# untitled.net
KiCad netlist of a schematic drawn in EAGLE
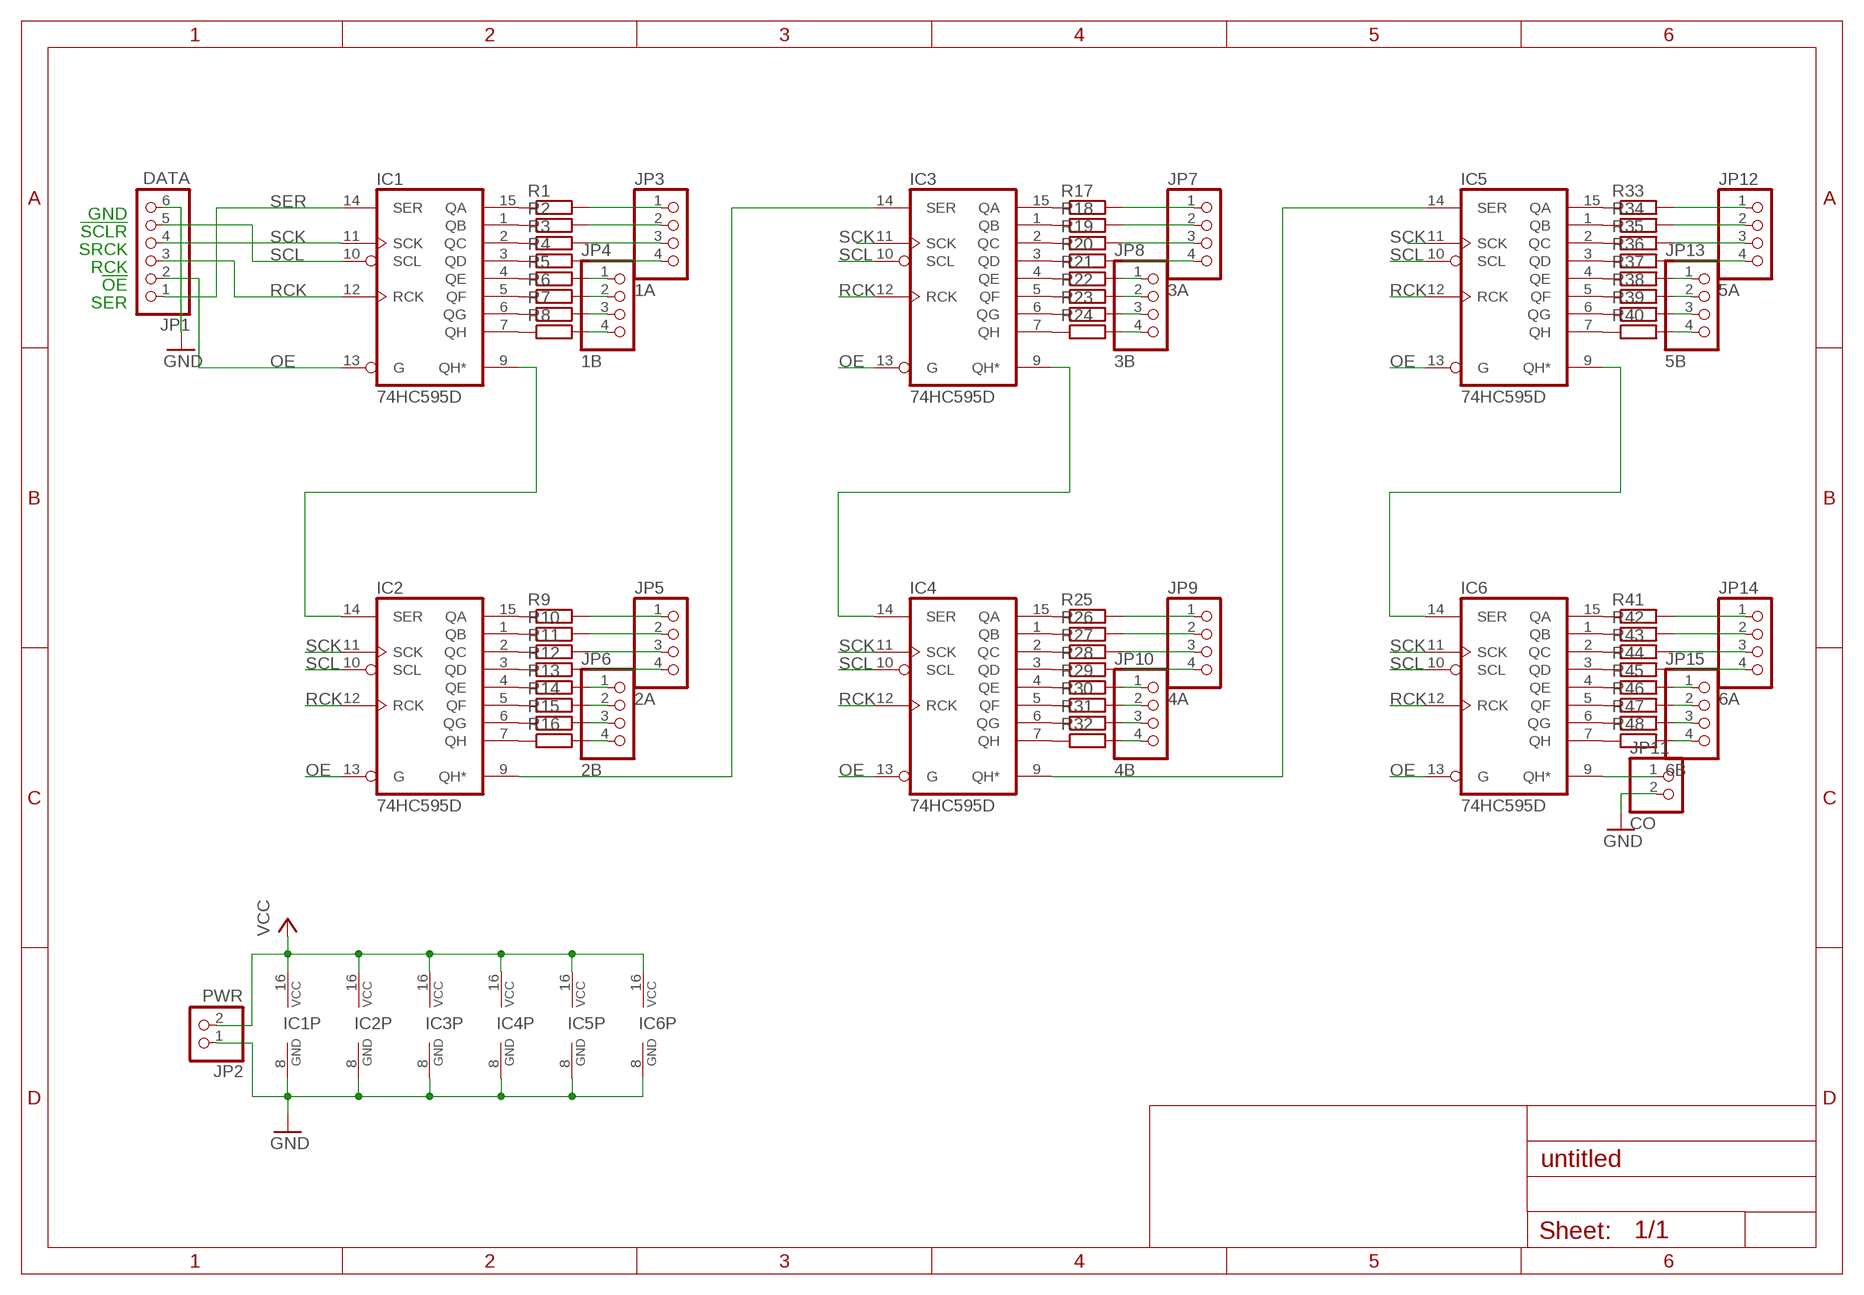
[diagram p0: schematic, sheet 1]

(export (version "E")
  (design (tool "Eeschema 10.0.6"))
  (components
    (comp (ref "IC1")
      (value "74HC595D")
      (footprint "eagle-import:SO16")
      (libsource (lib "eagle-import") (part "74595DHC"))
    )
    (comp (ref "IC2")
      (value "74HC595D")
      (footprint "eagle-import:SO16")
      (libsource (lib "eagle-import") (part "74595DHC"))
    )
    (comp (ref "IC3")
      (value "74HC595D")
      (footprint "eagle-import:SO16")
      (libsource (lib "eagle-import") (part "74595DHC"))
    )
    (comp (ref "IC4")
      (value "74HC595D")
      (footprint "eagle-import:SO16")
      (libsource (lib "eagle-import") (part "74595DHC"))
    )
    (comp (ref "IC5")
      (value "74HC595D")
      (footprint "eagle-import:SO16")
      (libsource (lib "eagle-import") (part "74595DHC"))
    )
    (comp (ref "IC6")
      (value "74HC595D")
      (footprint "eagle-import:SO16")
      (libsource (lib "eagle-import") (part "74595DHC"))
    )
    (comp (ref "JP1")
      (value "DATA")
      (footprint "eagle-import:1X06")
      (libsource (lib "eagle-import") (part "PINHD-1X6"))
    )
    (comp (ref "JP2")
      (value "PWR")
      (footprint "eagle-import:1X02")
      (libsource (lib "eagle-import") (part "PINHD-1X2"))
    )
    (comp (ref "JP3")
      (value "1A")
      (footprint "eagle-import:1X04")
      (libsource (lib "eagle-import") (part "PINHD-1X4"))
    )
    (comp (ref "JP4")
      (value "1B")
      (footprint "eagle-import:1X04")
      (libsource (lib "eagle-import") (part "PINHD-1X4"))
    )
    (comp (ref "JP5")
      (value "2A")
      (footprint "eagle-import:1X04")
      (libsource (lib "eagle-import") (part "PINHD-1X4"))
    )
    (comp (ref "JP6")
      (value "2B")
      (footprint "eagle-import:1X04")
      (libsource (lib "eagle-import") (part "PINHD-1X4"))
    )
    (comp (ref "JP7")
      (value "3A")
      (footprint "eagle-import:1X04")
      (libsource (lib "eagle-import") (part "PINHD-1X4"))
    )
    (comp (ref "JP8")
      (value "3B")
      (footprint "eagle-import:1X04")
      (libsource (lib "eagle-import") (part "PINHD-1X4"))
    )
    (comp (ref "JP9")
      (value "4A")
      (footprint "eagle-import:1X04")
      (libsource (lib "eagle-import") (part "PINHD-1X4"))
    )
    (comp (ref "JP10")
      (value "4B")
      (footprint "eagle-import:1X04")
      (libsource (lib "eagle-import") (part "PINHD-1X4"))
    )
    (comp (ref "JP11")
      (value "CO")
      (footprint "eagle-import:1X02")
      (libsource (lib "eagle-import") (part "PINHD-1X2"))
    )
    (comp (ref "JP12")
      (value "5A")
      (footprint "eagle-import:1X04")
      (libsource (lib "eagle-import") (part "PINHD-1X4"))
    )
    (comp (ref "JP13")
      (value "5B")
      (footprint "eagle-import:1X04")
      (libsource (lib "eagle-import") (part "PINHD-1X4"))
    )
    (comp (ref "JP14")
      (value "6A")
      (footprint "eagle-import:1X04")
      (libsource (lib "eagle-import") (part "PINHD-1X4"))
    )
    (comp (ref "JP15")
      (value "6B")
      (footprint "eagle-import:1X04")
      (libsource (lib "eagle-import") (part "PINHD-1X4"))
    )
    (comp (ref "R1")
      (value "R-EU_R0805")
      (footprint "eagle-import:R0805")
      (libsource (lib "eagle-import") (part "R-EU_R0805"))
    )
    (comp (ref "R2")
      (value "R-EU_R0805")
      (footprint "eagle-import:R0805")
      (libsource (lib "eagle-import") (part "R-EU_R0805"))
    )
    (comp (ref "R3")
      (value "R-EU_R0805")
      (footprint "eagle-import:R0805")
      (libsource (lib "eagle-import") (part "R-EU_R0805"))
    )
    (comp (ref "R4")
      (value "R-EU_R0805")
      (footprint "eagle-import:R0805")
      (libsource (lib "eagle-import") (part "R-EU_R0805"))
    )
    (comp (ref "R5")
      (value "R-EU_R0805")
      (footprint "eagle-import:R0805")
      (libsource (lib "eagle-import") (part "R-EU_R0805"))
    )
    (comp (ref "R6")
      (value "R-EU_R0805")
      (footprint "eagle-import:R0805")
      (libsource (lib "eagle-import") (part "R-EU_R0805"))
    )
    (comp (ref "R7")
      (value "R-EU_R0805")
      (footprint "eagle-import:R0805")
      (libsource (lib "eagle-import") (part "R-EU_R0805"))
    )
    (comp (ref "R8")
      (value "R-EU_R0805")
      (footprint "eagle-import:R0805")
      (libsource (lib "eagle-import") (part "R-EU_R0805"))
    )
    (comp (ref "R9")
      (value "R-EU_R0805")
      (footprint "eagle-import:R0805")
      (libsource (lib "eagle-import") (part "R-EU_R0805"))
    )
    (comp (ref "R10")
      (value "R-EU_R0805")
      (footprint "eagle-import:R0805")
      (libsource (lib "eagle-import") (part "R-EU_R0805"))
    )
    (comp (ref "R11")
      (value "R-EU_R0805")
      (footprint "eagle-import:R0805")
      (libsource (lib "eagle-import") (part "R-EU_R0805"))
    )
    (comp (ref "R12")
      (value "R-EU_R0805")
      (footprint "eagle-import:R0805")
      (libsource (lib "eagle-import") (part "R-EU_R0805"))
    )
    (comp (ref "R13")
      (value "R-EU_R0805")
      (footprint "eagle-import:R0805")
      (libsource (lib "eagle-import") (part "R-EU_R0805"))
    )
    (comp (ref "R14")
      (value "R-EU_R0805")
      (footprint "eagle-import:R0805")
      (libsource (lib "eagle-import") (part "R-EU_R0805"))
    )
    (comp (ref "R15")
      (value "R-EU_R0805")
      (footprint "eagle-import:R0805")
      (libsource (lib "eagle-import") (part "R-EU_R0805"))
    )
    (comp (ref "R16")
      (value "R-EU_R0805")
      (footprint "eagle-import:R0805")
      (libsource (lib "eagle-import") (part "R-EU_R0805"))
    )
    (comp (ref "R17")
      (value "R-EU_R0805")
      (footprint "eagle-import:R0805")
      (libsource (lib "eagle-import") (part "R-EU_R0805"))
    )
    (comp (ref "R18")
      (value "R-EU_R0805")
      (footprint "eagle-import:R0805")
      (libsource (lib "eagle-import") (part "R-EU_R0805"))
    )
    (comp (ref "R19")
      (value "R-EU_R0805")
      (footprint "eagle-import:R0805")
      (libsource (lib "eagle-import") (part "R-EU_R0805"))
    )
    (comp (ref "R20")
      (value "R-EU_R0805")
      (footprint "eagle-import:R0805")
      (libsource (lib "eagle-import") (part "R-EU_R0805"))
    )
    (comp (ref "R21")
      (value "R-EU_R0805")
      (footprint "eagle-import:R0805")
      (libsource (lib "eagle-import") (part "R-EU_R0805"))
    )
    (comp (ref "R22")
      (value "R-EU_R0805")
      (footprint "eagle-import:R0805")
      (libsource (lib "eagle-import") (part "R-EU_R0805"))
    )
    (comp (ref "R23")
      (value "R-EU_R0805")
      (footprint "eagle-import:R0805")
      (libsource (lib "eagle-import") (part "R-EU_R0805"))
    )
    (comp (ref "R24")
      (value "R-EU_R0805")
      (footprint "eagle-import:R0805")
      (libsource (lib "eagle-import") (part "R-EU_R0805"))
    )
    (comp (ref "R25")
      (value "R-EU_R0805")
      (footprint "eagle-import:R0805")
      (libsource (lib "eagle-import") (part "R-EU_R0805"))
    )
    (comp (ref "R26")
      (value "R-EU_R0805")
      (footprint "eagle-import:R0805")
      (libsource (lib "eagle-import") (part "R-EU_R0805"))
    )
    (comp (ref "R27")
      (value "R-EU_R0805")
      (footprint "eagle-import:R0805")
      (libsource (lib "eagle-import") (part "R-EU_R0805"))
    )
    (comp (ref "R28")
      (value "R-EU_R0805")
      (footprint "eagle-import:R0805")
      (libsource (lib "eagle-import") (part "R-EU_R0805"))
    )
    (comp (ref "R29")
      (value "R-EU_R0805")
      (footprint "eagle-import:R0805")
      (libsource (lib "eagle-import") (part "R-EU_R0805"))
    )
    (comp (ref "R30")
      (value "R-EU_R0805")
      (footprint "eagle-import:R0805")
      (libsource (lib "eagle-import") (part "R-EU_R0805"))
    )
    (comp (ref "R31")
      (value "R-EU_R0805")
      (footprint "eagle-import:R0805")
      (libsource (lib "eagle-import") (part "R-EU_R0805"))
    )
    (comp (ref "R32")
      (value "R-EU_R0805")
      (footprint "eagle-import:R0805")
      (libsource (lib "eagle-import") (part "R-EU_R0805"))
    )
    (comp (ref "R33")
      (value "R-EU_R0805")
      (footprint "eagle-import:R0805")
      (libsource (lib "eagle-import") (part "R-EU_R0805"))
    )
    (comp (ref "R34")
      (value "R-EU_R0805")
      (footprint "eagle-import:R0805")
      (libsource (lib "eagle-import") (part "R-EU_R0805"))
    )
    (comp (ref "R35")
      (value "R-EU_R0805")
      (footprint "eagle-import:R0805")
      (libsource (lib "eagle-import") (part "R-EU_R0805"))
    )
    (comp (ref "R36")
      (value "R-EU_R0805")
      (footprint "eagle-import:R0805")
      (libsource (lib "eagle-import") (part "R-EU_R0805"))
    )
    (comp (ref "R37")
      (value "R-EU_R0805")
      (footprint "eagle-import:R0805")
      (libsource (lib "eagle-import") (part "R-EU_R0805"))
    )
    (comp (ref "R38")
      (value "R-EU_R0805")
      (footprint "eagle-import:R0805")
      (libsource (lib "eagle-import") (part "R-EU_R0805"))
    )
    (comp (ref "R39")
      (value "R-EU_R0805")
      (footprint "eagle-import:R0805")
      (libsource (lib "eagle-import") (part "R-EU_R0805"))
    )
    (comp (ref "R40")
      (value "R-EU_R0805")
      (footprint "eagle-import:R0805")
      (libsource (lib "eagle-import") (part "R-EU_R0805"))
    )
    (comp (ref "R41")
      (value "R-EU_R0805")
      (footprint "eagle-import:R0805")
      (libsource (lib "eagle-import") (part "R-EU_R0805"))
    )
    (comp (ref "R42")
      (value "R-EU_R0805")
      (footprint "eagle-import:R0805")
      (libsource (lib "eagle-import") (part "R-EU_R0805"))
    )
    (comp (ref "R43")
      (value "R-EU_R0805")
      (footprint "eagle-import:R0805")
      (libsource (lib "eagle-import") (part "R-EU_R0805"))
    )
    (comp (ref "R44")
      (value "R-EU_R0805")
      (footprint "eagle-import:R0805")
      (libsource (lib "eagle-import") (part "R-EU_R0805"))
    )
    (comp (ref "R45")
      (value "R-EU_R0805")
      (footprint "eagle-import:R0805")
      (libsource (lib "eagle-import") (part "R-EU_R0805"))
    )
    (comp (ref "R46")
      (value "R-EU_R0805")
      (footprint "eagle-import:R0805")
      (libsource (lib "eagle-import") (part "R-EU_R0805"))
    )
    (comp (ref "R47")
      (value "R-EU_R0805")
      (footprint "eagle-import:R0805")
      (libsource (lib "eagle-import") (part "R-EU_R0805"))
    )
    (comp (ref "R48")
      (value "R-EU_R0805")
      (footprint "eagle-import:R0805")
      (libsource (lib "eagle-import") (part "R-EU_R0805"))
    )
  )
  (nets
    (net (code "1") (name "/OE") (class "Default")
      (node (ref "IC1") (pin "13") (pinfunction "G_13") (pintype "input"))
      (node (ref "IC2") (pin "13") (pinfunction "G_13") (pintype "input"))
      (node (ref "IC3") (pin "13") (pinfunction "G_13") (pintype "input"))
      (node (ref "IC4") (pin "13") (pinfunction "G_13") (pintype "input"))
      (node (ref "IC5") (pin "13") (pinfunction "G_13") (pintype "input"))
      (node (ref "IC6") (pin "13") (pinfunction "G_13") (pintype "input"))
      (node (ref "JP1") (pin "2") (pinfunction "2_2") (pintype "passive"))
    )
    (net (code "2") (name "/RCK") (class "Default")
      (node (ref "IC1") (pin "12") (pinfunction "RCK_12") (pintype "input"))
      (node (ref "IC2") (pin "12") (pinfunction "RCK_12") (pintype "input"))
      (node (ref "IC3") (pin "12") (pinfunction "RCK_12") (pintype "input"))
      (node (ref "IC4") (pin "12") (pinfunction "RCK_12") (pintype "input"))
      (node (ref "IC5") (pin "12") (pinfunction "RCK_12") (pintype "input"))
      (node (ref "IC6") (pin "12") (pinfunction "RCK_12") (pintype "input"))
      (node (ref "JP1") (pin "3") (pinfunction "3_3") (pintype "passive"))
    )
    (net (code "3") (name "/SCK") (class "Default")
      (node (ref "IC1") (pin "11") (pinfunction "SCK_11") (pintype "input"))
      (node (ref "IC2") (pin "11") (pinfunction "SCK_11") (pintype "input"))
      (node (ref "IC3") (pin "11") (pinfunction "SCK_11") (pintype "input"))
      (node (ref "IC4") (pin "11") (pinfunction "SCK_11") (pintype "input"))
      (node (ref "IC5") (pin "11") (pinfunction "SCK_11") (pintype "input"))
      (node (ref "IC6") (pin "11") (pinfunction "SCK_11") (pintype "input"))
      (node (ref "JP1") (pin "4") (pinfunction "4_4") (pintype "passive"))
    )
    (net (code "4") (name "/SCL") (class "Default")
      (node (ref "IC1") (pin "10") (pinfunction "SCL_10") (pintype "input"))
      (node (ref "IC2") (pin "10") (pinfunction "SCL_10") (pintype "input"))
      (node (ref "IC3") (pin "10") (pinfunction "SCL_10") (pintype "input"))
      (node (ref "IC4") (pin "10") (pinfunction "SCL_10") (pintype "input"))
      (node (ref "IC5") (pin "10") (pinfunction "SCL_10") (pintype "input"))
      (node (ref "IC6") (pin "10") (pinfunction "SCL_10") (pintype "input"))
      (node (ref "JP1") (pin "5") (pinfunction "5_5") (pintype "passive"))
    )
    (net (code "5") (name "/SER") (class "Default")
      (node (ref "IC1") (pin "14") (pinfunction "SER_14") (pintype "input"))
      (node (ref "JP1") (pin "1") (pinfunction "1_1") (pintype "passive"))
    )
    (net (code "6") (name "GND") (class "Default")
      (node (ref "IC1") (pin "8") (pinfunction "GND_8") (pintype "power_in"))
      (node (ref "IC2") (pin "8") (pinfunction "GND_8") (pintype "power_in"))
      (node (ref "IC3") (pin "8") (pinfunction "GND_8") (pintype "power_in"))
      (node (ref "IC4") (pin "8") (pinfunction "GND_8") (pintype "power_in"))
      (node (ref "IC5") (pin "8") (pinfunction "GND_8") (pintype "power_in"))
      (node (ref "IC6") (pin "8") (pinfunction "GND_8") (pintype "power_in"))
      (node (ref "JP1") (pin "6") (pinfunction "6_6") (pintype "passive"))
      (node (ref "JP11") (pin "2") (pinfunction "2_2") (pintype "passive"))
      (node (ref "JP2") (pin "1") (pinfunction "1_1") (pintype "passive"))
    )
    (net (code "7") (name "Net-(IC1A-QA)") (class "Default")
      (node (ref "IC1") (pin "15") (pinfunction "QA_15") (pintype "tri_state"))
      (node (ref "R1") (pin "1") (pinfunction "1_1") (pintype "passive"))
    )
    (net (code "8") (name "Net-(IC1A-QB)") (class "Default")
      (node (ref "IC1") (pin "1") (pinfunction "QB_1") (pintype "tri_state"))
      (node (ref "R2") (pin "1") (pinfunction "1_1") (pintype "passive"))
    )
    (net (code "9") (name "Net-(IC1A-QC)") (class "Default")
      (node (ref "IC1") (pin "2") (pinfunction "QC_2") (pintype "tri_state"))
      (node (ref "R3") (pin "1") (pinfunction "1_1") (pintype "passive"))
    )
    (net (code "10") (name "Net-(IC1A-QD)") (class "Default")
      (node (ref "IC1") (pin "3") (pinfunction "QD_3") (pintype "tri_state"))
      (node (ref "R4") (pin "1") (pinfunction "1_1") (pintype "passive"))
    )
    (net (code "11") (name "Net-(IC1A-QE)") (class "Default")
      (node (ref "IC1") (pin "4") (pinfunction "QE_4") (pintype "tri_state"))
      (node (ref "R5") (pin "1") (pinfunction "1_1") (pintype "passive"))
    )
    (net (code "12") (name "Net-(IC1A-QF)") (class "Default")
      (node (ref "IC1") (pin "5") (pinfunction "QF_5") (pintype "tri_state"))
      (node (ref "R6") (pin "1") (pinfunction "1_1") (pintype "passive"))
    )
    (net (code "13") (name "Net-(IC1A-QG)") (class "Default")
      (node (ref "IC1") (pin "6") (pinfunction "QG_6") (pintype "tri_state"))
      (node (ref "R7") (pin "1") (pinfunction "1_1") (pintype "passive"))
    )
    (net (code "14") (name "Net-(IC1A-QH)") (class "Default")
      (node (ref "IC1") (pin "7") (pinfunction "QH_7") (pintype "tri_state"))
      (node (ref "R8") (pin "1") (pinfunction "1_1") (pintype "passive"))
    )
    (net (code "15") (name "Net-(IC1A-QH*)") (class "Default")
      (node (ref "IC1") (pin "9") (pinfunction "QH*_9") (pintype "tri_state"))
      (node (ref "IC2") (pin "14") (pinfunction "SER_14") (pintype "input"))
    )
    (net (code "16") (name "Net-(IC2A-QA)") (class "Default")
      (node (ref "IC2") (pin "15") (pinfunction "QA_15") (pintype "tri_state"))
      (node (ref "R9") (pin "1") (pinfunction "1_1") (pintype "passive"))
    )
    (net (code "17") (name "Net-(IC2A-QB)") (class "Default")
      (node (ref "IC2") (pin "1") (pinfunction "QB_1") (pintype "tri_state"))
      (node (ref "R10") (pin "1") (pinfunction "1_1") (pintype "passive"))
    )
    (net (code "18") (name "Net-(IC2A-QC)") (class "Default")
      (node (ref "IC2") (pin "2") (pinfunction "QC_2") (pintype "tri_state"))
      (node (ref "R11") (pin "1") (pinfunction "1_1") (pintype "passive"))
    )
    (net (code "19") (name "Net-(IC2A-QD)") (class "Default")
      (node (ref "IC2") (pin "3") (pinfunction "QD_3") (pintype "tri_state"))
      (node (ref "R12") (pin "1") (pinfunction "1_1") (pintype "passive"))
    )
    (net (code "20") (name "Net-(IC2A-QE)") (class "Default")
      (node (ref "IC2") (pin "4") (pinfunction "QE_4") (pintype "tri_state"))
      (node (ref "R13") (pin "1") (pinfunction "1_1") (pintype "passive"))
    )
    (net (code "21") (name "Net-(IC2A-QF)") (class "Default")
      (node (ref "IC2") (pin "5") (pinfunction "QF_5") (pintype "tri_state"))
      (node (ref "R14") (pin "1") (pinfunction "1_1") (pintype "passive"))
    )
    (net (code "22") (name "Net-(IC2A-QG)") (class "Default")
      (node (ref "IC2") (pin "6") (pinfunction "QG_6") (pintype "tri_state"))
      (node (ref "R15") (pin "1") (pinfunction "1_1") (pintype "passive"))
    )
    (net (code "23") (name "Net-(IC2A-QH)") (class "Default")
      (node (ref "IC2") (pin "7") (pinfunction "QH_7") (pintype "tri_state"))
      (node (ref "R16") (pin "1") (pinfunction "1_1") (pintype "passive"))
    )
    (net (code "24") (name "Net-(IC2A-QH*)") (class "Default")
      (node (ref "IC2") (pin "9") (pinfunction "QH*_9") (pintype "tri_state"))
      (node (ref "IC3") (pin "14") (pinfunction "SER_14") (pintype "input"))
    )
    (net (code "25") (name "Net-(IC3A-QA)") (class "Default")
      (node (ref "IC3") (pin "15") (pinfunction "QA_15") (pintype "tri_state"))
      (node (ref "R17") (pin "1") (pinfunction "1_1") (pintype "passive"))
    )
    (net (code "26") (name "Net-(IC3A-QB)") (class "Default")
      (node (ref "IC3") (pin "1") (pinfunction "QB_1") (pintype "tri_state"))
      (node (ref "R18") (pin "1") (pinfunction "1_1") (pintype "passive"))
    )
    (net (code "27") (name "Net-(IC3A-QC)") (class "Default")
      (node (ref "IC3") (pin "2") (pinfunction "QC_2") (pintype "tri_state"))
      (node (ref "R19") (pin "1") (pinfunction "1_1") (pintype "passive"))
    )
    (net (code "28") (name "Net-(IC3A-QD)") (class "Default")
      (node (ref "IC3") (pin "3") (pinfunction "QD_3") (pintype "tri_state"))
      (node (ref "R20") (pin "1") (pinfunction "1_1") (pintype "passive"))
    )
    (net (code "29") (name "Net-(IC3A-QE)") (class "Default")
      (node (ref "IC3") (pin "4") (pinfunction "QE_4") (pintype "tri_state"))
      (node (ref "R21") (pin "1") (pinfunction "1_1") (pintype "passive"))
    )
    (net (code "30") (name "Net-(IC3A-QF)") (class "Default")
      (node (ref "IC3") (pin "5") (pinfunction "QF_5") (pintype "tri_state"))
      (node (ref "R22") (pin "1") (pinfunction "1_1") (pintype "passive"))
    )
    (net (code "31") (name "Net-(IC3A-QG)") (class "Default")
      (node (ref "IC3") (pin "6") (pinfunction "QG_6") (pintype "tri_state"))
      (node (ref "R23") (pin "1") (pinfunction "1_1") (pintype "passive"))
    )
    (net (code "32") (name "Net-(IC3A-QH)") (class "Default")
      (node (ref "IC3") (pin "7") (pinfunction "QH_7") (pintype "tri_state"))
      (node (ref "R24") (pin "1") (pinfunction "1_1") (pintype "passive"))
    )
    (net (code "33") (name "Net-(IC3A-QH*)") (class "Default")
      (node (ref "IC3") (pin "9") (pinfunction "QH*_9") (pintype "tri_state"))
      (node (ref "IC4") (pin "14") (pinfunction "SER_14") (pintype "input"))
    )
    (net (code "34") (name "Net-(IC4A-QA)") (class "Default")
      (node (ref "IC4") (pin "15") (pinfunction "QA_15") (pintype "tri_state"))
      (node (ref "R25") (pin "1") (pinfunction "1_1") (pintype "passive"))
    )
    (net (code "35") (name "Net-(IC4A-QB)") (class "Default")
      (node (ref "IC4") (pin "1") (pinfunction "QB_1") (pintype "tri_state"))
      (node (ref "R26") (pin "1") (pinfunction "1_1") (pintype "passive"))
    )
    (net (code "36") (name "Net-(IC4A-QC)") (class "Default")
      (node (ref "IC4") (pin "2") (pinfunction "QC_2") (pintype "tri_state"))
      (node (ref "R27") (pin "1") (pinfunction "1_1") (pintype "passive"))
    )
    (net (code "37") (name "Net-(IC4A-QD)") (class "Default")
      (node (ref "IC4") (pin "3") (pinfunction "QD_3") (pintype "tri_state"))
      (node (ref "R28") (pin "1") (pinfunction "1_1") (pintype "passive"))
    )
    (net (code "38") (name "Net-(IC4A-QE)") (class "Default")
      (node (ref "IC4") (pin "4") (pinfunction "QE_4") (pintype "tri_state"))
      (node (ref "R29") (pin "1") (pinfunction "1_1") (pintype "passive"))
    )
    (net (code "39") (name "Net-(IC4A-QF)") (class "Default")
      (node (ref "IC4") (pin "5") (pinfunction "QF_5") (pintype "tri_state"))
      (node (ref "R30") (pin "1") (pinfunction "1_1") (pintype "passive"))
    )
    (net (code "40") (name "Net-(IC4A-QG)") (class "Default")
      (node (ref "IC4") (pin "6") (pinfunction "QG_6") (pintype "tri_state"))
      (node (ref "R31") (pin "1") (pinfunction "1_1") (pintype "passive"))
    )
    (net (code "41") (name "Net-(IC4A-QH)") (class "Default")
      (node (ref "IC4") (pin "7") (pinfunction "QH_7") (pintype "tri_state"))
      (node (ref "R32") (pin "1") (pinfunction "1_1") (pintype "passive"))
    )
    (net (code "42") (name "Net-(IC4A-QH*)") (class "Default")
      (node (ref "IC4") (pin "9") (pinfunction "QH*_9") (pintype "tri_state"))
      (node (ref "IC5") (pin "14") (pinfunction "SER_14") (pintype "input"))
    )
    (net (code "43") (name "Net-(IC5A-QA)") (class "Default")
      (node (ref "IC5") (pin "15") (pinfunction "QA_15") (pintype "tri_state"))
      (node (ref "R33") (pin "1") (pinfunction "1_1") (pintype "passive"))
    )
    (net (code "44") (name "Net-(IC5A-QB)") (class "Default")
      (node (ref "IC5") (pin "1") (pinfunction "QB_1") (pintype "tri_state"))
      (node (ref "R34") (pin "1") (pinfunction "1_1") (pintype "passive"))
    )
    (net (code "45") (name "Net-(IC5A-QC)") (class "Default")
      (node (ref "IC5") (pin "2") (pinfunction "QC_2") (pintype "tri_state"))
      (node (ref "R35") (pin "1") (pinfunction "1_1") (pintype "passive"))
    )
    (net (code "46") (name "Net-(IC5A-QD)") (class "Default")
      (node (ref "IC5") (pin "3") (pinfunction "QD_3") (pintype "tri_state"))
      (node (ref "R36") (pin "1") (pinfunction "1_1") (pintype "passive"))
    )
    (net (code "47") (name "Net-(IC5A-QE)") (class "Default")
      (node (ref "IC5") (pin "4") (pinfunction "QE_4") (pintype "tri_state"))
      (node (ref "R37") (pin "1") (pinfunction "1_1") (pintype "passive"))
    )
    (net (code "48") (name "Net-(IC5A-QF)") (class "Default")
      (node (ref "IC5") (pin "5") (pinfunction "QF_5") (pintype "tri_state"))
      (node (ref "R38") (pin "1") (pinfunction "1_1") (pintype "passive"))
    )
    (net (code "49") (name "Net-(IC5A-QG)") (class "Default")
      (node (ref "IC5") (pin "6") (pinfunction "QG_6") (pintype "tri_state"))
      (node (ref "R39") (pin "1") (pinfunction "1_1") (pintype "passive"))
    )
    (net (code "50") (name "Net-(IC5A-QH)") (class "Default")
      (node (ref "IC5") (pin "7") (pinfunction "QH_7") (pintype "tri_state"))
      (node (ref "R40") (pin "1") (pinfunction "1_1") (pintype "passive"))
    )
    (net (code "51") (name "Net-(IC5A-QH*)") (class "Default")
      (node (ref "IC5") (pin "9") (pinfunction "QH*_9") (pintype "tri_state"))
      (node (ref "IC6") (pin "14") (pinfunction "SER_14") (pintype "input"))
    )
    (net (code "52") (name "Net-(IC6A-QA)") (class "Default")
      (node (ref "IC6") (pin "15") (pinfunction "QA_15") (pintype "tri_state"))
      (node (ref "R41") (pin "1") (pinfunction "1_1") (pintype "passive"))
    )
    (net (code "53") (name "Net-(IC6A-QB)") (class "Default")
      (node (ref "IC6") (pin "1") (pinfunction "QB_1") (pintype "tri_state"))
      (node (ref "R42") (pin "1") (pinfunction "1_1") (pintype "passive"))
    )
    (net (code "54") (name "Net-(IC6A-QC)") (class "Default")
      (node (ref "IC6") (pin "2") (pinfunction "QC_2") (pintype "tri_state"))
      (node (ref "R43") (pin "1") (pinfunction "1_1") (pintype "passive"))
    )
    (net (code "55") (name "Net-(IC6A-QD)") (class "Default")
      (node (ref "IC6") (pin "3") (pinfunction "QD_3") (pintype "tri_state"))
      (node (ref "R44") (pin "1") (pinfunction "1_1") (pintype "passive"))
    )
    (net (code "56") (name "Net-(IC6A-QE)") (class "Default")
      (node (ref "IC6") (pin "4") (pinfunction "QE_4") (pintype "tri_state"))
      (node (ref "R45") (pin "1") (pinfunction "1_1") (pintype "passive"))
    )
    (net (code "57") (name "Net-(IC6A-QF)") (class "Default")
      (node (ref "IC6") (pin "5") (pinfunction "QF_5") (pintype "tri_state"))
      (node (ref "R46") (pin "1") (pinfunction "1_1") (pintype "passive"))
    )
    (net (code "58") (name "Net-(IC6A-QG)") (class "Default")
      (node (ref "IC6") (pin "6") (pinfunction "QG_6") (pintype "tri_state"))
      (node (ref "R47") (pin "1") (pinfunction "1_1") (pintype "passive"))
    )
    (net (code "59") (name "Net-(IC6A-QH)") (class "Default")
      (node (ref "IC6") (pin "7") (pinfunction "QH_7") (pintype "tri_state"))
      (node (ref "R48") (pin "1") (pinfunction "1_1") (pintype "passive"))
    )
    (net (code "60") (name "Net-(IC6A-QH*)") (class "Default")
      (node (ref "IC6") (pin "9") (pinfunction "QH*_9") (pintype "tri_state"))
      (node (ref "JP11") (pin "1") (pinfunction "1_1") (pintype "passive"))
    )
    (net (code "61") (name "Net-(JP3-Pad1)") (class "Default")
      (node (ref "JP3") (pin "1") (pinfunction "1_1") (pintype "passive"))
      (node (ref "R1") (pin "2") (pinfunction "2_2") (pintype "passive"))
    )
    (net (code "62") (name "Net-(JP3-Pad2)") (class "Default")
      (node (ref "JP3") (pin "2") (pinfunction "2_2") (pintype "passive"))
      (node (ref "R2") (pin "2") (pinfunction "2_2") (pintype "passive"))
    )
    (net (code "63") (name "Net-(JP3-Pad3)") (class "Default")
      (node (ref "JP3") (pin "3") (pinfunction "3_3") (pintype "passive"))
      (node (ref "R3") (pin "2") (pinfunction "2_2") (pintype "passive"))
    )
    (net (code "64") (name "Net-(JP3-Pad4)") (class "Default")
      (node (ref "JP3") (pin "4") (pinfunction "4_4") (pintype "passive"))
      (node (ref "R4") (pin "2") (pinfunction "2_2") (pintype "passive"))
    )
    (net (code "65") (name "Net-(JP4-Pad1)") (class "Default")
      (node (ref "JP4") (pin "1") (pinfunction "1_1") (pintype "passive"))
      (node (ref "R5") (pin "2") (pinfunction "2_2") (pintype "passive"))
    )
    (net (code "66") (name "Net-(JP4-Pad2)") (class "Default")
      (node (ref "JP4") (pin "2") (pinfunction "2_2") (pintype "passive"))
      (node (ref "R6") (pin "2") (pinfunction "2_2") (pintype "passive"))
    )
    (net (code "67") (name "Net-(JP4-Pad3)") (class "Default")
      (node (ref "JP4") (pin "3") (pinfunction "3_3") (pintype "passive"))
      (node (ref "R7") (pin "2") (pinfunction "2_2") (pintype "passive"))
    )
    (net (code "68") (name "Net-(JP4-Pad4)") (class "Default")
      (node (ref "JP4") (pin "4") (pinfunction "4_4") (pintype "passive"))
      (node (ref "R8") (pin "2") (pinfunction "2_2") (pintype "passive"))
    )
    (net (code "69") (name "Net-(JP5-Pad1)") (class "Default")
      (node (ref "JP5") (pin "1") (pinfunction "1_1") (pintype "passive"))
      (node (ref "R9") (pin "2") (pinfunction "2_2") (pintype "passive"))
    )
    (net (code "70") (name "Net-(JP5-Pad2)") (class "Default")
      (node (ref "JP5") (pin "2") (pinfunction "2_2") (pintype "passive"))
      (node (ref "R10") (pin "2") (pinfunction "2_2") (pintype "passive"))
    )
    (net (code "71") (name "Net-(JP5-Pad3)") (class "Default")
      (node (ref "JP5") (pin "3") (pinfunction "3_3") (pintype "passive"))
      (node (ref "R11") (pin "2") (pinfunction "2_2") (pintype "passive"))
    )
    (net (code "72") (name "Net-(JP5-Pad4)") (class "Default")
      (node (ref "JP5") (pin "4") (pinfunction "4_4") (pintype "passive"))
      (node (ref "R12") (pin "2") (pinfunction "2_2") (pintype "passive"))
    )
    (net (code "73") (name "Net-(JP6-Pad1)") (class "Default")
      (node (ref "JP6") (pin "1") (pinfunction "1_1") (pintype "passive"))
      (node (ref "R13") (pin "2") (pinfunction "2_2") (pintype "passive"))
    )
    (net (code "74") (name "Net-(JP6-Pad2)") (class "Default")
      (node (ref "JP6") (pin "2") (pinfunction "2_2") (pintype "passive"))
      (node (ref "R14") (pin "2") (pinfunction "2_2") (pintype "passive"))
    )
    (net (code "75") (name "Net-(JP6-Pad3)") (class "Default")
      (node (ref "JP6") (pin "3") (pinfunction "3_3") (pintype "passive"))
      (node (ref "R15") (pin "2") (pinfunction "2_2") (pintype "passive"))
    )
    (net (code "76") (name "Net-(JP6-Pad4)") (class "Default")
      (node (ref "JP6") (pin "4") (pinfunction "4_4") (pintype "passive"))
      (node (ref "R16") (pin "2") (pinfunction "2_2") (pintype "passive"))
    )
    (net (code "77") (name "Net-(JP7-Pad1)") (class "Default")
      (node (ref "JP7") (pin "1") (pinfunction "1_1") (pintype "passive"))
      (node (ref "R17") (pin "2") (pinfunction "2_2") (pintype "passive"))
    )
    (net (code "78") (name "Net-(JP7-Pad2)") (class "Default")
      (node (ref "JP7") (pin "2") (pinfunction "2_2") (pintype "passive"))
      (node (ref "R18") (pin "2") (pinfunction "2_2") (pintype "passive"))
    )
    (net (code "79") (name "Net-(JP7-Pad3)") (class "Default")
      (node (ref "JP7") (pin "3") (pinfunction "3_3") (pintype "passive"))
      (node (ref "R19") (pin "2") (pinfunction "2_2") (pintype "passive"))
    )
    (net (code "80") (name "Net-(JP7-Pad4)") (class "Default")
      (node (ref "JP7") (pin "4") (pinfunction "4_4") (pintype "passive"))
      (node (ref "R20") (pin "2") (pinfunction "2_2") (pintype "passive"))
    )
    (net (code "81") (name "Net-(JP8-Pad1)") (class "Default")
      (node (ref "JP8") (pin "1") (pinfunction "1_1") (pintype "passive"))
      (node (ref "R21") (pin "2") (pinfunction "2_2") (pintype "passive"))
    )
    (net (code "82") (name "Net-(JP8-Pad2)") (class "Default")
      (node (ref "JP8") (pin "2") (pinfunction "2_2") (pintype "passive"))
      (node (ref "R22") (pin "2") (pinfunction "2_2") (pintype "passive"))
    )
    (net (code "83") (name "Net-(JP8-Pad3)") (class "Default")
      (node (ref "JP8") (pin "3") (pinfunction "3_3") (pintype "passive"))
      (node (ref "R23") (pin "2") (pinfunction "2_2") (pintype "passive"))
    )
    (net (code "84") (name "Net-(JP8-Pad4)") (class "Default")
      (node (ref "JP8") (pin "4") (pinfunction "4_4") (pintype "passive"))
      (node (ref "R24") (pin "2") (pinfunction "2_2") (pintype "passive"))
    )
    (net (code "85") (name "Net-(JP9-Pad1)") (class "Default")
      (node (ref "JP9") (pin "1") (pinfunction "1_1") (pintype "passive"))
      (node (ref "R25") (pin "2") (pinfunction "2_2") (pintype "passive"))
    )
    (net (code "86") (name "Net-(JP9-Pad2)") (class "Default")
      (node (ref "JP9") (pin "2") (pinfunction "2_2") (pintype "passive"))
      (node (ref "R26") (pin "2") (pinfunction "2_2") (pintype "passive"))
    )
    (net (code "87") (name "Net-(JP9-Pad3)") (class "Default")
      (node (ref "JP9") (pin "3") (pinfunction "3_3") (pintype "passive"))
      (node (ref "R27") (pin "2") (pinfunction "2_2") (pintype "passive"))
    )
    (net (code "88") (name "Net-(JP9-Pad4)") (class "Default")
      (node (ref "JP9") (pin "4") (pinfunction "4_4") (pintype "passive"))
      (node (ref "R28") (pin "2") (pinfunction "2_2") (pintype "passive"))
    )
    (net (code "89") (name "Net-(JP10-Pad1)") (class "Default")
      (node (ref "JP10") (pin "1") (pinfunction "1_1") (pintype "passive"))
      (node (ref "R29") (pin "2") (pinfunction "2_2") (pintype "passive"))
    )
    (net (code "90") (name "Net-(JP10-Pad2)") (class "Default")
      (node (ref "JP10") (pin "2") (pinfunction "2_2") (pintype "passive"))
      (node (ref "R30") (pin "2") (pinfunction "2_2") (pintype "passive"))
    )
    (net (code "91") (name "Net-(JP10-Pad3)") (class "Default")
      (node (ref "JP10") (pin "3") (pinfunction "3_3") (pintype "passive"))
      (node (ref "R31") (pin "2") (pinfunction "2_2") (pintype "passive"))
    )
    (net (code "92") (name "Net-(JP10-Pad4)") (class "Default")
      (node (ref "JP10") (pin "4") (pinfunction "4_4") (pintype "passive"))
      (node (ref "R32") (pin "2") (pinfunction "2_2") (pintype "passive"))
    )
    (net (code "93") (name "Net-(JP12-Pad1)") (class "Default")
      (node (ref "JP12") (pin "1") (pinfunction "1_1") (pintype "passive"))
      (node (ref "R33") (pin "2") (pinfunction "2_2") (pintype "passive"))
    )
    (net (code "94") (name "Net-(JP12-Pad2)") (class "Default")
      (node (ref "JP12") (pin "2") (pinfunction "2_2") (pintype "passive"))
      (node (ref "R34") (pin "2") (pinfunction "2_2") (pintype "passive"))
    )
    (net (code "95") (name "Net-(JP12-Pad3)") (class "Default")
      (node (ref "JP12") (pin "3") (pinfunction "3_3") (pintype "passive"))
      (node (ref "R35") (pin "2") (pinfunction "2_2") (pintype "passive"))
    )
    (net (code "96") (name "Net-(JP12-Pad4)") (class "Default")
      (node (ref "JP12") (pin "4") (pinfunction "4_4") (pintype "passive"))
      (node (ref "R36") (pin "2") (pinfunction "2_2") (pintype "passive"))
    )
    (net (code "97") (name "Net-(JP13-Pad1)") (class "Default")
      (node (ref "JP13") (pin "1") (pinfunction "1_1") (pintype "passive"))
      (node (ref "R37") (pin "2") (pinfunction "2_2") (pintype "passive"))
    )
    (net (code "98") (name "Net-(JP13-Pad2)") (class "Default")
      (node (ref "JP13") (pin "2") (pinfunction "2_2") (pintype "passive"))
      (node (ref "R38") (pin "2") (pinfunction "2_2") (pintype "passive"))
    )
    (net (code "99") (name "Net-(JP13-Pad3)") (class "Default")
      (node (ref "JP13") (pin "3") (pinfunction "3_3") (pintype "passive"))
      (node (ref "R39") (pin "2") (pinfunction "2_2") (pintype "passive"))
    )
    (net (code "100") (name "Net-(JP13-Pad4)") (class "Default")
      (node (ref "JP13") (pin "4") (pinfunction "4_4") (pintype "passive"))
      (node (ref "R40") (pin "2") (pinfunction "2_2") (pintype "passive"))
    )
    (net (code "101") (name "Net-(JP14-Pad1)") (class "Default")
      (node (ref "JP14") (pin "1") (pinfunction "1_1") (pintype "passive"))
      (node (ref "R41") (pin "2") (pinfunction "2_2") (pintype "passive"))
    )
    (net (code "102") (name "Net-(JP14-Pad2)") (class "Default")
      (node (ref "JP14") (pin "2") (pinfunction "2_2") (pintype "passive"))
      (node (ref "R42") (pin "2") (pinfunction "2_2") (pintype "passive"))
    )
    (net (code "103") (name "Net-(JP14-Pad3)") (class "Default")
      (node (ref "JP14") (pin "3") (pinfunction "3_3") (pintype "passive"))
      (node (ref "R43") (pin "2") (pinfunction "2_2") (pintype "passive"))
    )
    (net (code "104") (name "Net-(JP14-Pad4)") (class "Default")
      (node (ref "JP14") (pin "4") (pinfunction "4_4") (pintype "passive"))
      (node (ref "R44") (pin "2") (pinfunction "2_2") (pintype "passive"))
    )
    (net (code "105") (name "Net-(JP15-Pad1)") (class "Default")
      (node (ref "JP15") (pin "1") (pinfunction "1_1") (pintype "passive"))
      (node (ref "R45") (pin "2") (pinfunction "2_2") (pintype "passive"))
    )
    (net (code "106") (name "Net-(JP15-Pad2)") (class "Default")
      (node (ref "JP15") (pin "2") (pinfunction "2_2") (pintype "passive"))
      (node (ref "R46") (pin "2") (pinfunction "2_2") (pintype "passive"))
    )
    (net (code "107") (name "Net-(JP15-Pad3)") (class "Default")
      (node (ref "JP15") (pin "3") (pinfunction "3_3") (pintype "passive"))
      (node (ref "R47") (pin "2") (pinfunction "2_2") (pintype "passive"))
    )
    (net (code "108") (name "Net-(JP15-Pad4)") (class "Default")
      (node (ref "JP15") (pin "4") (pinfunction "4_4") (pintype "passive"))
      (node (ref "R48") (pin "2") (pinfunction "2_2") (pintype "passive"))
    )
    (net (code "109") (name "VCC") (class "Default")
      (node (ref "IC1") (pin "16") (pinfunction "VCC_16") (pintype "power_in"))
      (node (ref "IC2") (pin "16") (pinfunction "VCC_16") (pintype "power_in"))
      (node (ref "IC3") (pin "16") (pinfunction "VCC_16") (pintype "power_in"))
      (node (ref "IC4") (pin "16") (pinfunction "VCC_16") (pintype "power_in"))
      (node (ref "IC5") (pin "16") (pinfunction "VCC_16") (pintype "power_in"))
      (node (ref "IC6") (pin "16") (pinfunction "VCC_16") (pintype "power_in"))
      (node (ref "JP2") (pin "2") (pinfunction "2_2") (pintype "passive"))
    )
  )
)
